# ethernet_connectors.net
KiCad netlist of a schematic drawn in Altium Designer
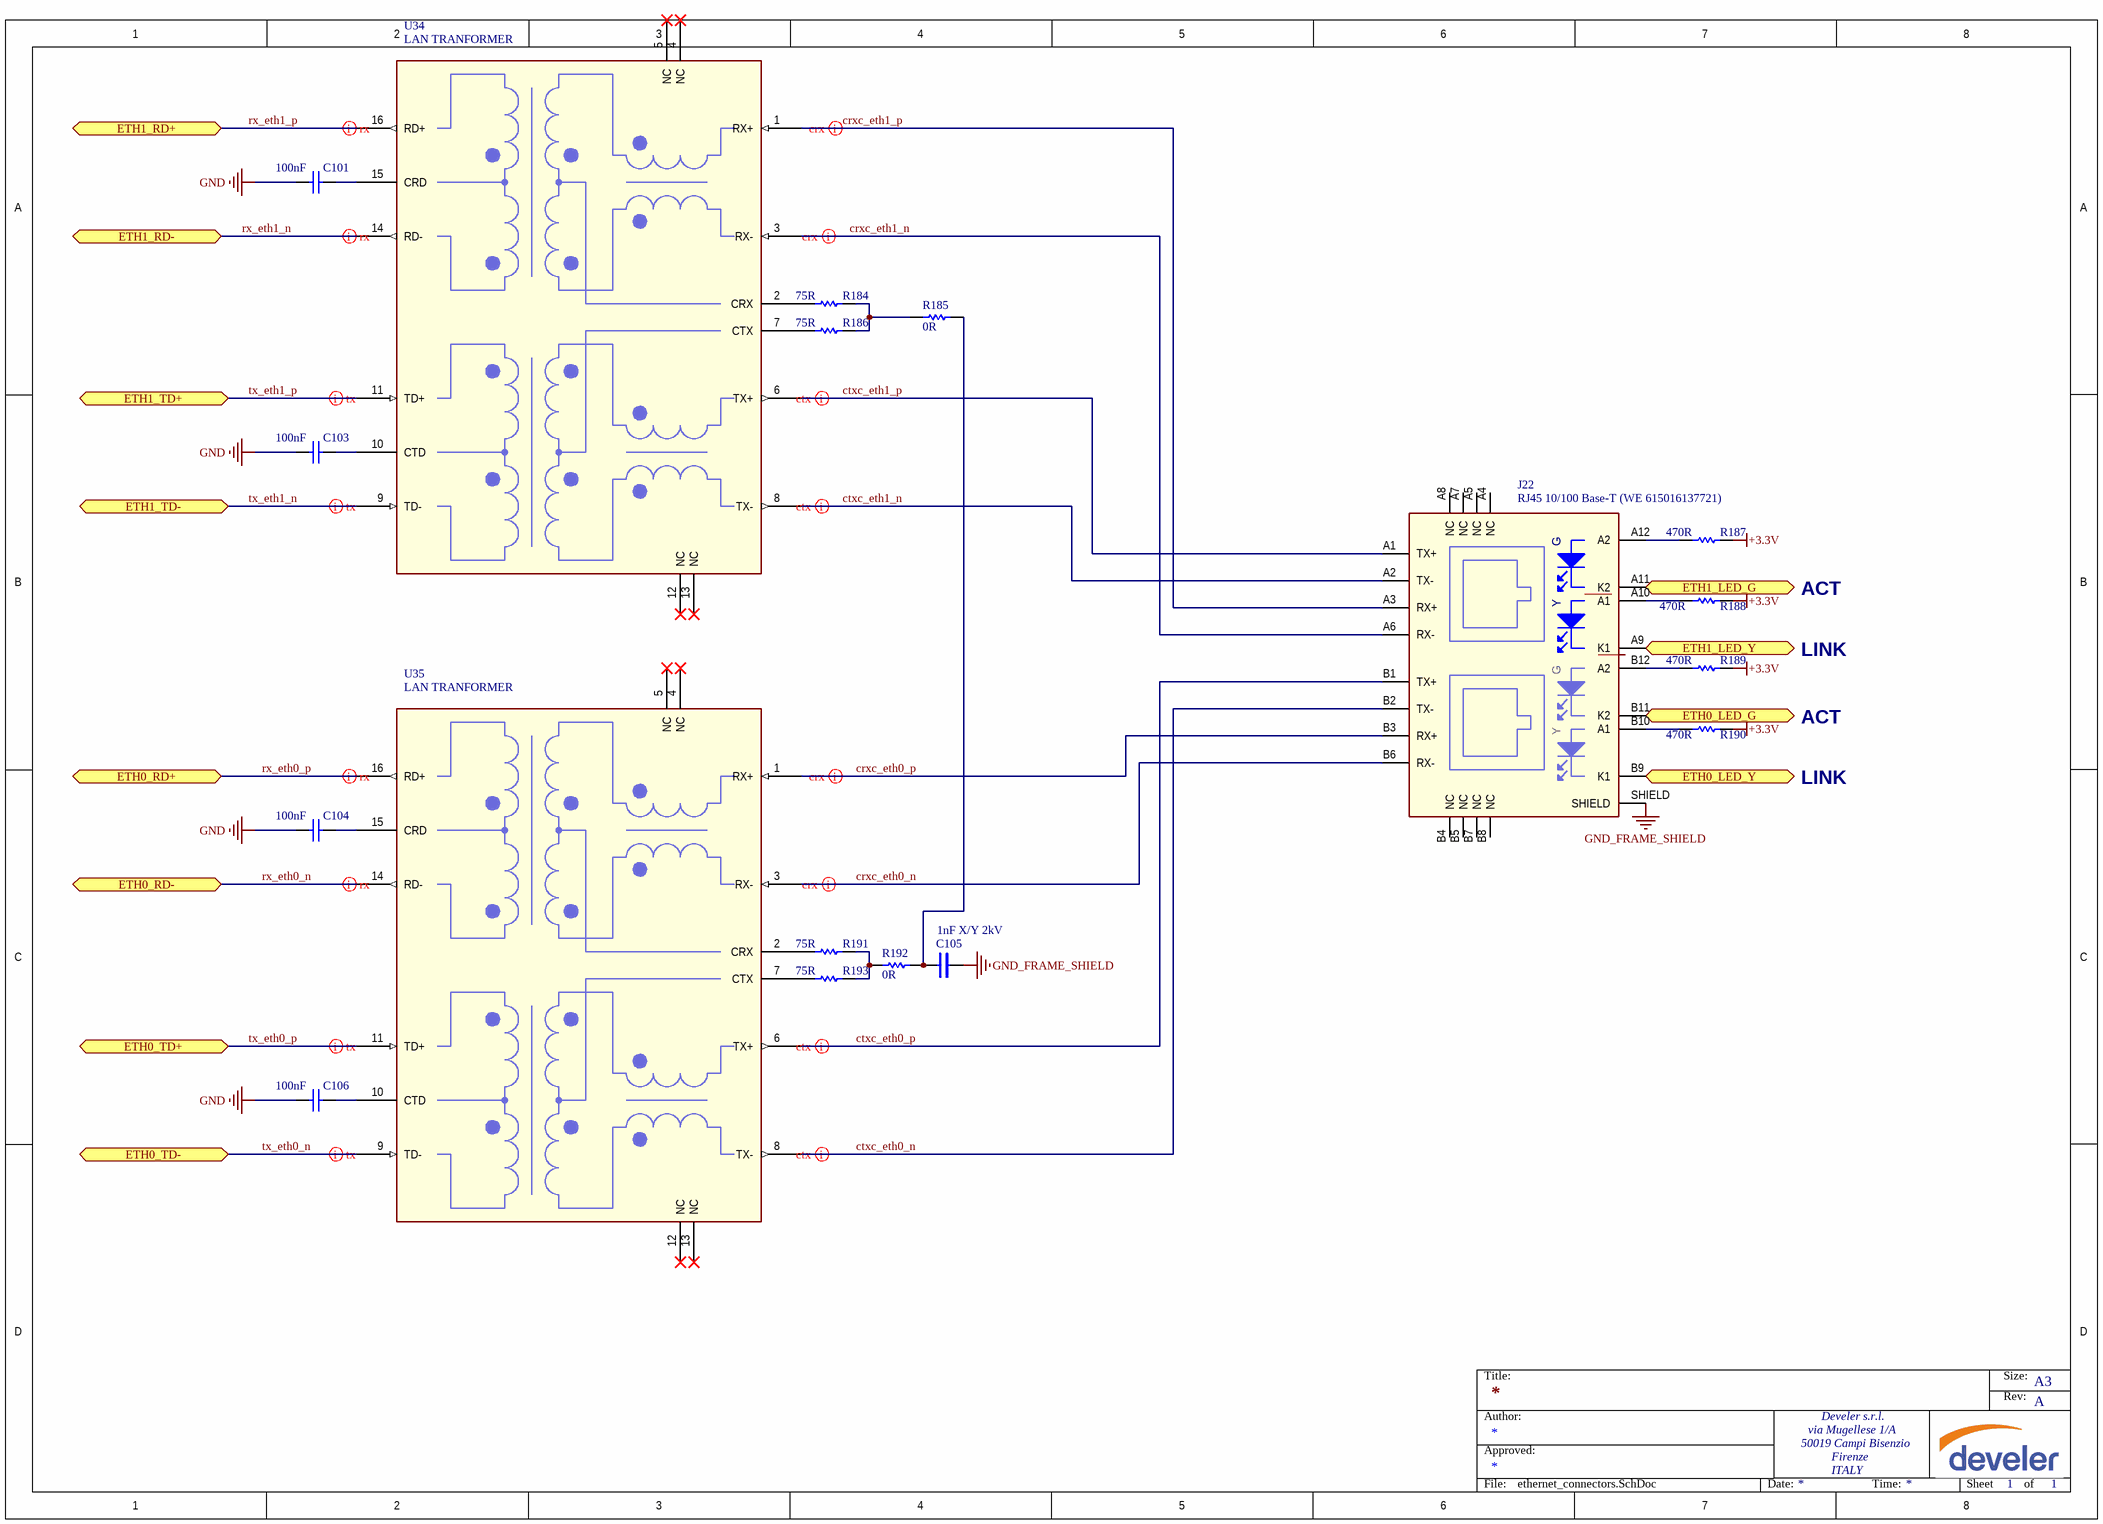
[diagram p0: ethernet_connectors.SchDoc]

(export (version "E")
  (design (tool "Eeschema 10.0.6"))
  (components
    (comp (ref "C101")
      (value "100nF")
      (footprint "0603_[1608]")
      (description "Ceramic X7R 50V")
      (fields (field (name "PUBLISHER") "Altium Limited"))
      (libsource (lib "project42_lib") (part "Cap"))
    )
    (comp (ref "C103")
      (value "100nF")
      (footprint "0603_[1608]")
      (description "Ceramic X7R 50V")
      (fields (field (name "PUBLISHER") "Altium Limited"))
      (libsource (lib "project42_lib") (part "Cap"))
    )
    (comp (ref "C104")
      (value "100nF")
      (footprint "0603_[1608]")
      (description "Ceramic X7R 50V")
      (fields (field (name "PUBLISHER") "Altium Limited"))
      (libsource (lib "project42_lib") (part "Cap"))
    )
    (comp (ref "C105")
      (value "1nF X/Y 2kV")
      (footprint "1808_[4520]")
      (description "CER 250VAC X7R X1/Y1 (GA342DR7GF102KW)")
      (libsource (lib "DEVELER_Library") (part "cap_xy"))
    )
    (comp (ref "C106")
      (value "100nF")
      (footprint "0603_[1608]")
      (description "Ceramic X7R 50V")
      (fields (field (name "PUBLISHER") "Altium Limited"))
      (libsource (lib "project42_lib") (part "Cap"))
    )
    (comp (ref "J22")
      (value "RJ45 10/100 Base-T (WE 615016137721)")
      (footprint "RJ45_HORIZONTAL_CON_DUAL")
      (description "RJ45 10/100 Base-T Dual (WE 615016137721)")
      (libsource (lib "DEVELER_Library") (part "RJ45_10/100Base-T_Dual_connector"))
    )
    (comp (ref "R184")
      (value "75R")
      (footprint "0603_[1608]")
      (description "Resistor")
      (libsource (lib "DEVELER_Library") (part "Res1"))
    )
    (comp (ref "R185")
      (value "0R")
      (footprint "0603_[1608]")
      (description "Resistor")
      (fields (field (name "PUBLISHER") "Altium Limited"))
      (libsource (lib "") (part "Res1_1"))
    )
    (comp (ref "R186")
      (value "75R")
      (footprint "0603_[1608]")
      (description "Resistor")
      (libsource (lib "DEVELER_Library") (part "Res1"))
    )
    (comp (ref "R187")
      (value "470R")
      (footprint "0603_[1608]")
      (description "Resistor")
      (fields (field (name "PUBLISHER") "Altium Limited"))
      (libsource (lib "") (part "Res1_2"))
    )
    (comp (ref "R188")
      (value "470R")
      (footprint "0603_[1608]")
      (description "Resistor")
      (fields (field (name "PUBLISHER") "Altium Limited"))
      (libsource (lib "") (part "Res1_2"))
    )
    (comp (ref "R189")
      (value "470R")
      (footprint "0603_[1608]")
      (description "Resistor")
      (fields (field (name "PUBLISHER") "Altium Limited"))
      (libsource (lib "") (part "Res1_2"))
    )
    (comp (ref "R190")
      (value "470R")
      (footprint "0603_[1608]")
      (description "Resistor")
      (fields (field (name "PUBLISHER") "Altium Limited"))
      (libsource (lib "") (part "Res1_2"))
    )
    (comp (ref "R191")
      (value "75R")
      (footprint "0603_[1608]")
      (description "Resistor")
      (libsource (lib "DEVELER_Library") (part "Res1"))
    )
    (comp (ref "R192")
      (value "0R")
      (footprint "0603_[1608]")
      (description "Resistor")
      (fields (field (name "PUBLISHER") "Altium Limited"))
      (libsource (lib "") (part "Res1_1"))
    )
    (comp (ref "R193")
      (value "75R")
      (footprint "0603_[1608]")
      (description "Resistor")
      (libsource (lib "DEVELER_Library") (part "Res1"))
    )
    (comp (ref "U34")
      (value "LAN TRANFORMER")
      (footprint "LAN_TR_1.27MM_SMD")
      (description "WE 749010011; WE 7490100111A; WE 7490100161A;")
      (libsource (lib "DEVELER_Library") (part "LAN-TR-WE749010014"))
    )
    (comp (ref "U35")
      (value "LAN TRANFORMER")
      (footprint "LAN_TR_1.27MM_SMD")
      (description "WE 749010011; WE 7490100111A; WE 7490100161A;")
      (libsource (lib "DEVELER_Library") (part "LAN-TR-WE749010014"))
    )
  )
  (nets
    (net (code "1") (name "+3.3V") (class "Default")
      (node (ref "R187") (pin "1") (pinfunction "1_1") (pintype "passive"))
      (node (ref "R188") (pin "1") (pinfunction "1_1") (pintype "passive"))
      (node (ref "R189") (pin "1") (pinfunction "1_1") (pintype "passive"))
      (node (ref "R190") (pin "1") (pinfunction "1_1") (pintype "passive"))
    )
    (net (code "2") (name "/ETH0_LED_G") (class "Default")
      (node (ref "J22") (pin "B11") (pinfunction "K2_B11") (pintype "passive"))
    )
    (net (code "3") (name "/ETH0_LED_Y") (class "Default")
      (node (ref "J22") (pin "B9") (pinfunction "K1_B9") (pintype "passive"))
    )
    (net (code "4") (name "/ETH1_LED_G") (class "Default")
      (node (ref "J22") (pin "A11") (pinfunction "K2_A11") (pintype "passive"))
    )
    (net (code "5") (name "/ETH1_LED_Y") (class "Default")
      (node (ref "J22") (pin "A9") (pinfunction "K1_A9") (pintype "passive"))
    )
    (net (code "6") (name "/crxc_eth0_n") (class "Default")
      (node (ref "J22") (pin "B6") (pinfunction "RX-_B6") (pintype "passive"))
      (node (ref "U35") (pin "3") (pinfunction "RX-_3") (pintype "input"))
    )
    (net (code "7") (name "/crxc_eth0_p") (class "Default")
      (node (ref "J22") (pin "B3") (pinfunction "RX+_B3") (pintype "passive"))
      (node (ref "U35") (pin "1") (pinfunction "RX+_1") (pintype "input"))
    )
    (net (code "8") (name "/crxc_eth1_n") (class "Default")
      (node (ref "J22") (pin "A6") (pinfunction "RX-_A6") (pintype "passive"))
      (node (ref "U34") (pin "3") (pinfunction "RX-_3") (pintype "input"))
    )
    (net (code "9") (name "/crxc_eth1_p") (class "Default")
      (node (ref "J22") (pin "A3") (pinfunction "RX+_A3") (pintype "passive"))
      (node (ref "U34") (pin "1") (pinfunction "RX+_1") (pintype "input"))
    )
    (net (code "10") (name "/ctxc_eth0_n") (class "Default")
      (node (ref "J22") (pin "B2") (pinfunction "TX-_B2") (pintype "passive"))
      (node (ref "U35") (pin "8") (pinfunction "TX-_8") (pintype "output"))
    )
    (net (code "11") (name "/ctxc_eth0_p") (class "Default")
      (node (ref "J22") (pin "B1") (pinfunction "TX+_B1") (pintype "passive"))
      (node (ref "U35") (pin "6") (pinfunction "TX+_6") (pintype "output"))
    )
    (net (code "12") (name "/ctxc_eth1_n") (class "Default")
      (node (ref "J22") (pin "A2") (pinfunction "TX-_A2") (pintype "passive"))
      (node (ref "U34") (pin "8") (pinfunction "TX-_8") (pintype "output"))
    )
    (net (code "13") (name "/ctxc_eth1_p") (class "Default")
      (node (ref "J22") (pin "A1") (pinfunction "TX+_A1") (pintype "passive"))
      (node (ref "U34") (pin "6") (pinfunction "TX+_6") (pintype "output"))
    )
    (net (code "14") (name "/rx_eth0_n") (class "Default")
      (node (ref "U35") (pin "14") (pinfunction "RD-_14") (pintype "output"))
    )
    (net (code "15") (name "/rx_eth0_p") (class "Default")
      (node (ref "U35") (pin "16") (pinfunction "RD+_16") (pintype "output"))
    )
    (net (code "16") (name "/rx_eth1_n") (class "Default")
      (node (ref "U34") (pin "14") (pinfunction "RD-_14") (pintype "output"))
    )
    (net (code "17") (name "/rx_eth1_p") (class "Default")
      (node (ref "U34") (pin "16") (pinfunction "RD+_16") (pintype "output"))
    )
    (net (code "18") (name "/tx_eth0_n") (class "Default")
      (node (ref "U35") (pin "9") (pinfunction "TD-_9") (pintype "input"))
    )
    (net (code "19") (name "/tx_eth0_p") (class "Default")
      (node (ref "U35") (pin "11") (pinfunction "TD+_11") (pintype "input"))
    )
    (net (code "20") (name "/tx_eth1_n") (class "Default")
      (node (ref "U34") (pin "9") (pinfunction "TD-_9") (pintype "input"))
    )
    (net (code "21") (name "/tx_eth1_p") (class "Default")
      (node (ref "U34") (pin "11") (pinfunction "TD+_11") (pintype "input"))
    )
    (net (code "22") (name "GND") (class "Default")
      (node (ref "C101") (pin "2") (pinfunction "2_2") (pintype "passive"))
      (node (ref "C103") (pin "2") (pinfunction "2_2") (pintype "passive"))
      (node (ref "C104") (pin "2") (pinfunction "2_2") (pintype "passive"))
      (node (ref "C106") (pin "2") (pinfunction "2_2") (pintype "passive"))
    )
    (net (code "23") (name "GND_FRAME_SHIELD") (class "Default")
      (node (ref "C105") (pin "2") (pinfunction "2_2") (pintype "passive"))
      (node (ref "J22") (pin "SHIELD") (pinfunction "SHIELD_SHIELD") (pintype "passive"))
    )
    (net (code "24") (name "Net-(C105-Pad1)") (class "Default")
      (node (ref "C105") (pin "1") (pinfunction "1_1") (pintype "passive"))
      (node (ref "R185") (pin "1") (pinfunction "1_1") (pintype "passive"))
      (node (ref "R192") (pin "1") (pinfunction "1_1") (pintype "passive"))
    )
    (net (code "25") (name "Net-(J22-A1-PadA10)") (class "Default")
      (node (ref "J22") (pin "A10") (pinfunction "A1_A10") (pintype "passive"))
      (node (ref "R188") (pin "2") (pinfunction "2_2") (pintype "passive"))
    )
    (net (code "26") (name "Net-(J22-A1-PadB10)") (class "Default")
      (node (ref "J22") (pin "B10") (pinfunction "A1_B10") (pintype "passive"))
      (node (ref "R190") (pin "2") (pinfunction "2_2") (pintype "passive"))
    )
    (net (code "27") (name "Net-(J22-A2-PadA12)") (class "Default")
      (node (ref "J22") (pin "A12") (pinfunction "A2_A12") (pintype "passive"))
      (node (ref "R187") (pin "2") (pinfunction "2_2") (pintype "passive"))
    )
    (net (code "28") (name "Net-(J22-A2-PadB12)") (class "Default")
      (node (ref "J22") (pin "B12") (pinfunction "A2_B12") (pintype "passive"))
      (node (ref "R189") (pin "2") (pinfunction "2_2") (pintype "passive"))
    )
    (net (code "29") (name "Net-(R184-Pad1)") (class "Default")
      (node (ref "R184") (pin "1") (pinfunction "1_1") (pintype "passive"))
      (node (ref "R185") (pin "2") (pinfunction "2_2") (pintype "passive"))
      (node (ref "R186") (pin "1") (pinfunction "1_1") (pintype "passive"))
    )
    (net (code "30") (name "Net-(R191-Pad1)") (class "Default")
      (node (ref "R191") (pin "1") (pinfunction "1_1") (pintype "passive"))
      (node (ref "R192") (pin "2") (pinfunction "2_2") (pintype "passive"))
      (node (ref "R193") (pin "1") (pinfunction "1_1") (pintype "passive"))
    )
    (net (code "31") (name "Net-(U34-CRD)") (class "Default")
      (node (ref "C101") (pin "1") (pinfunction "1_1") (pintype "passive"))
      (node (ref "U34") (pin "15") (pinfunction "CRD_15") (pintype "passive"))
    )
    (net (code "32") (name "Net-(U34-CRX)") (class "Default")
      (node (ref "R184") (pin "2") (pinfunction "2_2") (pintype "passive"))
      (node (ref "U34") (pin "2") (pinfunction "CRX_2") (pintype "passive"))
    )
    (net (code "33") (name "Net-(U34-CTD)") (class "Default")
      (node (ref "C103") (pin "1") (pinfunction "1_1") (pintype "passive"))
      (node (ref "U34") (pin "10") (pinfunction "CTD_10") (pintype "passive"))
    )
    (net (code "34") (name "Net-(U34-CTX)") (class "Default")
      (node (ref "R186") (pin "2") (pinfunction "2_2") (pintype "passive"))
      (node (ref "U34") (pin "7") (pinfunction "CTX_7") (pintype "passive"))
    )
    (net (code "35") (name "Net-(U35-CRD)") (class "Default")
      (node (ref "C104") (pin "1") (pinfunction "1_1") (pintype "passive"))
      (node (ref "U35") (pin "15") (pinfunction "CRD_15") (pintype "passive"))
    )
    (net (code "36") (name "Net-(U35-CRX)") (class "Default")
      (node (ref "R191") (pin "2") (pinfunction "2_2") (pintype "passive"))
      (node (ref "U35") (pin "2") (pinfunction "CRX_2") (pintype "passive"))
    )
    (net (code "37") (name "Net-(U35-CTD)") (class "Default")
      (node (ref "C106") (pin "1") (pinfunction "1_1") (pintype "passive"))
      (node (ref "U35") (pin "10") (pinfunction "CTD_10") (pintype "passive"))
    )
    (net (code "38") (name "Net-(U35-CTX)") (class "Default")
      (node (ref "R193") (pin "2") (pinfunction "2_2") (pintype "passive"))
      (node (ref "U35") (pin "7") (pinfunction "CTX_7") (pintype "passive"))
    )
    (net (code "39") (name "unconnected-(J22-NC-PadA4)") (class "Default")
      (node (ref "J22") (pin "A4") (pinfunction "NC_A4") (pintype "passive"))
    )
    (net (code "40") (name "unconnected-(J22-NC-PadA5)") (class "Default")
      (node (ref "J22") (pin "A5") (pinfunction "NC_A5") (pintype "passive"))
    )
    (net (code "41") (name "unconnected-(J22-NC-PadA7)") (class "Default")
      (node (ref "J22") (pin "A7") (pinfunction "NC_A7") (pintype "passive"))
    )
    (net (code "42") (name "unconnected-(J22-NC-PadA8)") (class "Default")
      (node (ref "J22") (pin "A8") (pinfunction "NC_A8") (pintype "passive"))
    )
    (net (code "43") (name "unconnected-(J22-NC-PadB4)") (class "Default")
      (node (ref "J22") (pin "B4") (pinfunction "NC_B4") (pintype "passive"))
    )
    (net (code "44") (name "unconnected-(J22-NC-PadB5)") (class "Default")
      (node (ref "J22") (pin "B5") (pinfunction "NC_B5") (pintype "passive"))
    )
    (net (code "45") (name "unconnected-(J22-NC-PadB7)") (class "Default")
      (node (ref "J22") (pin "B7") (pinfunction "NC_B7") (pintype "passive"))
    )
    (net (code "46") (name "unconnected-(J22-NC-PadB8)") (class "Default")
      (node (ref "J22") (pin "B8") (pinfunction "NC_B8") (pintype "passive"))
    )
    (net (code "47") (name "unconnected-(U34-NC-Pad4)") (class "Default")
      (node (ref "U34") (pin "4") (pinfunction "NC_4") (pintype "passive+no_connect"))
    )
    (net (code "48") (name "unconnected-(U34-NC-Pad5)") (class "Default")
      (node (ref "U34") (pin "5") (pinfunction "NC_5") (pintype "passive+no_connect"))
    )
    (net (code "49") (name "unconnected-(U34-NC-Pad12)") (class "Default")
      (node (ref "U34") (pin "12") (pinfunction "NC_12") (pintype "passive+no_connect"))
    )
    (net (code "50") (name "unconnected-(U34-NC-Pad13)") (class "Default")
      (node (ref "U34") (pin "13") (pinfunction "NC_13") (pintype "passive+no_connect"))
    )
    (net (code "51") (name "unconnected-(U35-NC-Pad4)") (class "Default")
      (node (ref "U35") (pin "4") (pinfunction "NC_4") (pintype "passive+no_connect"))
    )
    (net (code "52") (name "unconnected-(U35-NC-Pad5)") (class "Default")
      (node (ref "U35") (pin "5") (pinfunction "NC_5") (pintype "passive+no_connect"))
    )
    (net (code "53") (name "unconnected-(U35-NC-Pad12)") (class "Default")
      (node (ref "U35") (pin "12") (pinfunction "NC_12") (pintype "passive+no_connect"))
    )
    (net (code "54") (name "unconnected-(U35-NC-Pad13)") (class "Default")
      (node (ref "U35") (pin "13") (pinfunction "NC_13") (pintype "passive+no_connect"))
    )
  )
)
